# TopLevel.net
KiCad netlist of a schematic drawn in Altium Designer
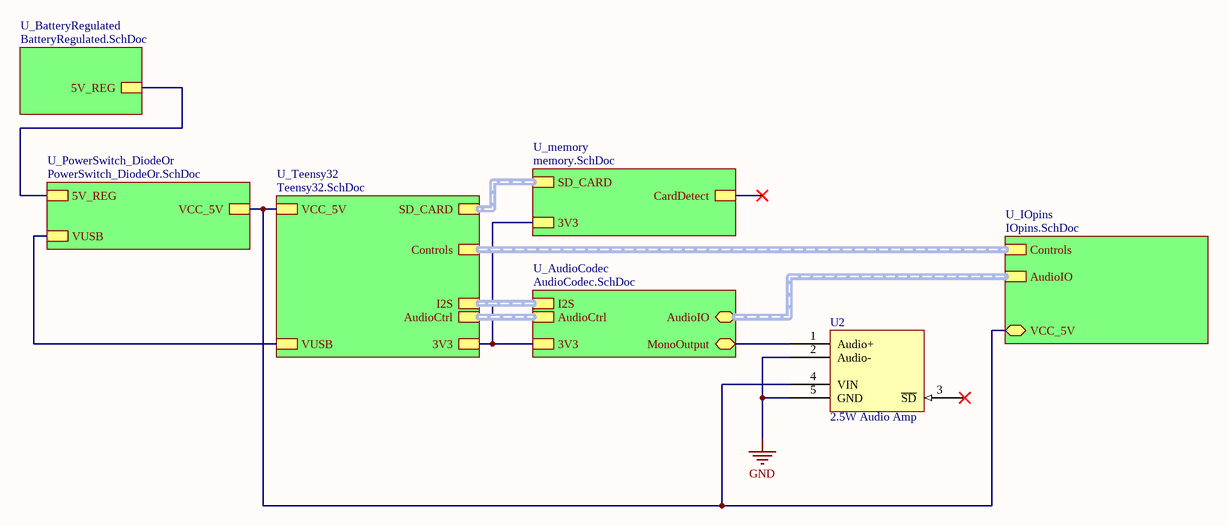
[diagram p0: TopLevel.SchDoc]

(export (version "E")
  (design (tool "Eeschema 10.0.6"))
  (components
    (comp (ref "U2")
      (value "2.5W Audio Amp")
      (footprint "Adafruit_PAM8302A")
      (description "2.5W Class D Audio Amplifier")
      (libsource (lib "Pololu") (part "Adafruit_PAM8302"))
    )
  )
  (nets
    (net (code "8") (name "/MonoOutput") (class "Default")
      (node (ref "U2") (pin "1") (pinfunction "Audio+_1") (pintype "passive"))
    )
    (net (code "10") (name "/VCC_5V") (class "Default")
      (node (ref "U2") (pin "4") (pinfunction "VIN_4") (pintype "power_in"))
    )
    (net (code "12") (name "GND") (class "Default")
      (node (ref "U2") (pin "2") (pinfunction "Audio-_2") (pintype "passive"))
      (node (ref "U2") (pin "5") (pinfunction "GND_5") (pintype "power_in"))
    )
    (net (code "13") (name "unconnected-(U2-~{SD}-Pad3)") (class "Default")
      (node (ref "U2") (pin "3") (pinfunction "~{SD}_3") (pintype "input+no_connect"))
    )
  )
)
